# DNET_Processor.net
KiCad netlist of a schematic drawn in Altium Designer
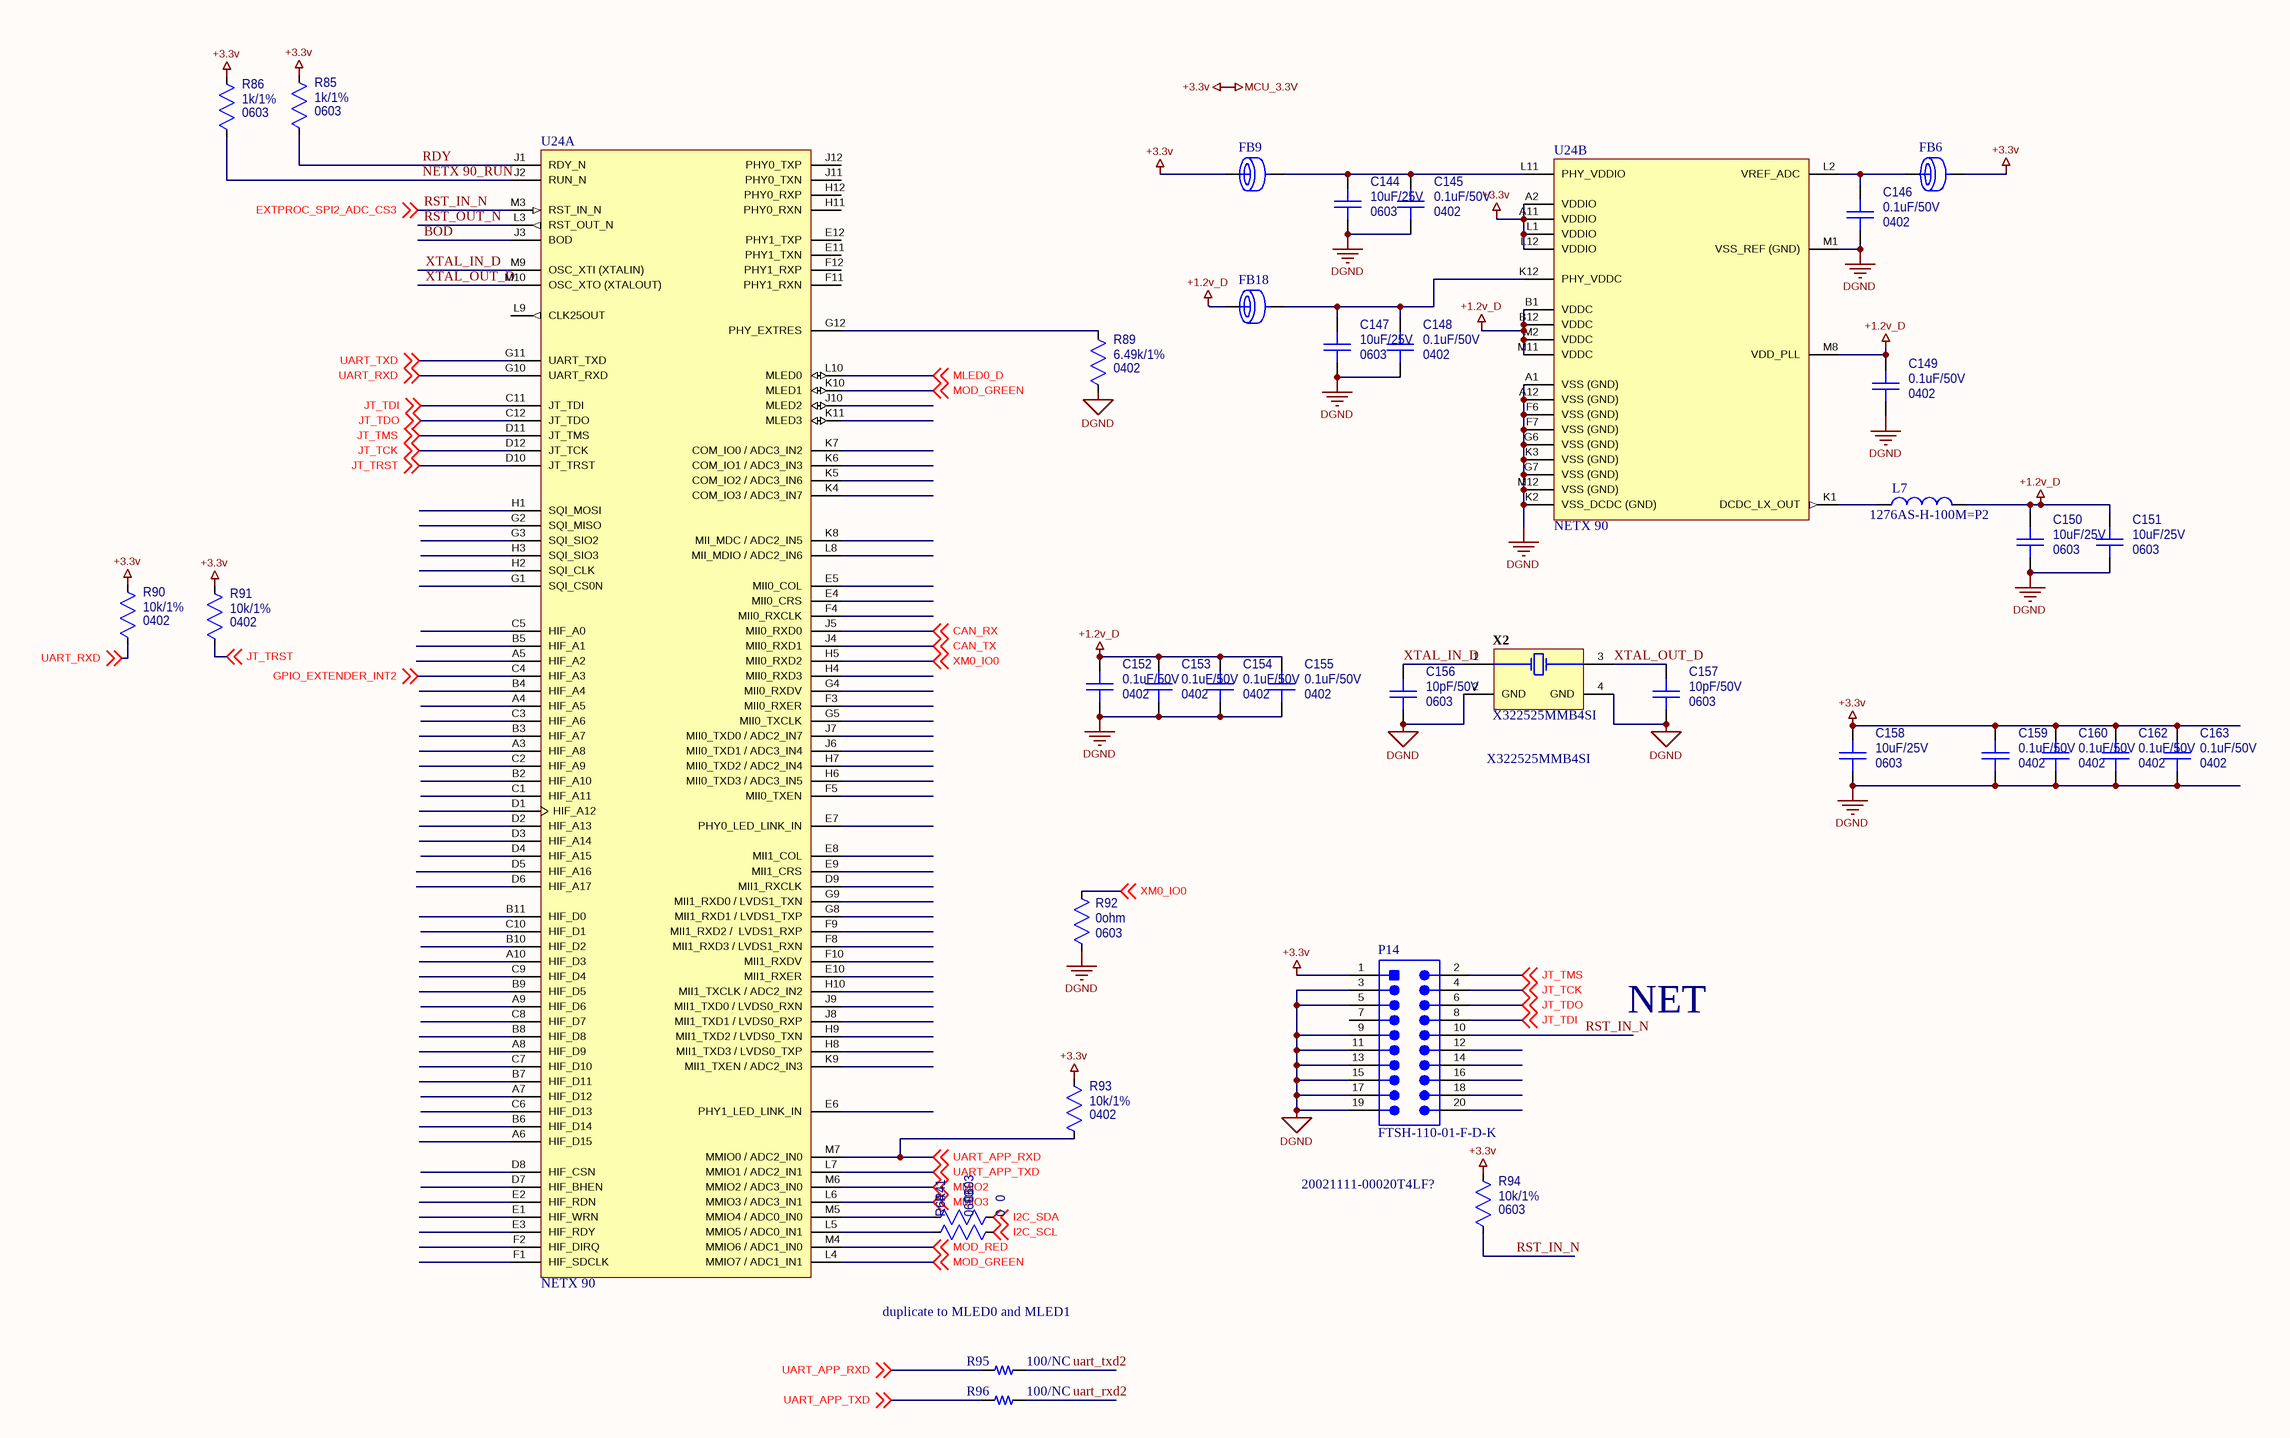
[diagram p0: DNET_Processor.SchDoc]

(export (version "E")
  (design (tool "Eeschema 10.0.6"))
  (components
    (comp (ref "C144")
      (value "10uF/25V")
      (footprint "CAPC1608X092N_0603")
      (fields
        (field (name "PARTNUMBER") "GRM188R61E106MA73D")
        (field (name "TOLERANCE") "[tol]")
        (field (name "PACKAGE") "0603")
      )
      (libsource (lib "Karl") (part "Capacitor_0603"))
    )
    (comp (ref "C145")
      (value "0.1uF/50V")
      (footprint "CAPC1005X056N_0402")
      (fields (field (name "TOLERANCE") "[tol]") (field (name "PACKAGE") "0402"))
      (libsource (lib "Karl") (part "Capacitor_0402"))
    )
    (comp (ref "C146")
      (value "0.1uF/50V")
      (footprint "CAPC1005X056N_0402")
      (fields (field (name "TOLERANCE") "[tol]") (field (name "PACKAGE") "0402"))
      (libsource (lib "Karl") (part "Capacitor_0402"))
    )
    (comp (ref "C147")
      (value "10uF/25V")
      (footprint "CAPC1608X092N_0603")
      (fields
        (field (name "PARTNUMBER") "GRM188R61E106MA73D")
        (field (name "TOLERANCE") "[tol]")
        (field (name "PACKAGE") "0603")
      )
      (libsource (lib "Karl") (part "Capacitor_0603"))
    )
    (comp (ref "C148")
      (value "0.1uF/50V")
      (footprint "CAPC1005X056N_0402")
      (fields (field (name "TOLERANCE") "[tol]") (field (name "PACKAGE") "0402"))
      (libsource (lib "Karl") (part "Capacitor_0402"))
    )
    (comp (ref "C149")
      (value "0.1uF/50V")
      (footprint "CAPC1005X056N_0402")
      (fields (field (name "TOLERANCE") "[tol]") (field (name "PACKAGE") "0402"))
      (libsource (lib "Karl") (part "Capacitor_0402"))
    )
    (comp (ref "C150")
      (value "10uF/25V")
      (footprint "CAPC1608X092N_0603")
      (fields
        (field (name "PARTNUMBER") "GRM188R61E106MA73D")
        (field (name "TOLERANCE") "[tol]")
        (field (name "PACKAGE") "0603")
      )
      (libsource (lib "Karl") (part "Capacitor_0603"))
    )
    (comp (ref "C151")
      (value "10uF/25V")
      (footprint "CAPC1608X092N_0603")
      (fields
        (field (name "PARTNUMBER") "GRM188R61E106MA73D")
        (field (name "TOLERANCE") "[tol]")
        (field (name "PACKAGE") "0603")
      )
      (libsource (lib "Karl") (part "Capacitor_0603"))
    )
    (comp (ref "C152")
      (value "0.1uF/50V")
      (footprint "CAPC1005X056N_0402")
      (fields (field (name "TOLERANCE") "[tol]") (field (name "PACKAGE") "0402"))
      (libsource (lib "Karl") (part "Capacitor_0402"))
    )
    (comp (ref "C153")
      (value "0.1uF/50V")
      (footprint "CAPC1005X056N_0402")
      (fields (field (name "TOLERANCE") "[tol]") (field (name "PACKAGE") "0402"))
      (libsource (lib "Karl") (part "Capacitor_0402"))
    )
    (comp (ref "C154")
      (value "0.1uF/50V")
      (footprint "CAPC1005X056N_0402")
      (fields (field (name "TOLERANCE") "[tol]") (field (name "PACKAGE") "0402"))
      (libsource (lib "Karl") (part "Capacitor_0402"))
    )
    (comp (ref "C155")
      (value "0.1uF/50V")
      (footprint "CAPC1005X056N_0402")
      (fields (field (name "TOLERANCE") "[tol]") (field (name "PACKAGE") "0402"))
      (libsource (lib "Karl") (part "Capacitor_0402"))
    )
    (comp (ref "C156")
      (value "10pF/50V")
      (footprint "CAPC1608X092N_0603")
      (fields (field (name "TOLERANCE") "[tol]") (field (name "PACKAGE") "0603"))
      (libsource (lib "Karl") (part "Capacitor_0603"))
    )
    (comp (ref "C157")
      (value "10pF/50V")
      (footprint "CAPC1608X092N_0603")
      (fields (field (name "TOLERANCE") "[tol]") (field (name "PACKAGE") "0603"))
      (libsource (lib "Karl") (part "Capacitor_0603"))
    )
    (comp (ref "C158")
      (value "10uF/25V")
      (footprint "CAPC1608X092N_0603")
      (fields
        (field (name "PARTNUMBER") "GRM188R61E106MA73D")
        (field (name "TOLERANCE") "[tol]")
        (field (name "PACKAGE") "0603")
      )
      (libsource (lib "Karl") (part "Capacitor_0603"))
    )
    (comp (ref "C159")
      (value "0.1uF/50V")
      (footprint "CAPC1005X056N_0402")
      (fields (field (name "TOLERANCE") "[tol]") (field (name "PACKAGE") "0402"))
      (libsource (lib "Karl") (part "Capacitor_0402"))
    )
    (comp (ref "C160")
      (value "0.1uF/50V")
      (footprint "CAPC1005X056N_0402")
      (fields (field (name "TOLERANCE") "[tol]") (field (name "PACKAGE") "0402"))
      (libsource (lib "Karl") (part "Capacitor_0402"))
    )
    (comp (ref "C162")
      (value "0.1uF/50V")
      (footprint "CAPC1005X056N_0402")
      (fields (field (name "TOLERANCE") "[tol]") (field (name "PACKAGE") "0402"))
      (libsource (lib "Karl") (part "Capacitor_0402"))
    )
    (comp (ref "C163")
      (value "0.1uF/50V")
      (footprint "CAPC1005X056N_0402")
      (fields (field (name "TOLERANCE") "[tol]") (field (name "PACKAGE") "0402"))
      (libsource (lib "Karl") (part "Capacitor_0402"))
    )
    (comp (ref "FB6")
      (value "FBC0603")
      (footprint "FBC0603")
      (fields (field (name "PARTNUMBER") "PE-0603PFB121ST"))
      (libsource (lib "Karl") (part "FBC0603"))
    )
    (comp (ref "FB9")
      (value "FBC0603")
      (footprint "FBC0603")
      (fields (field (name "PARTNUMBER") "PE-0603PFB121ST"))
      (libsource (lib "Karl") (part "FBC0603"))
    )
    (comp (ref "FB18")
      (value "FBC0603")
      (footprint "FBC0603")
      (fields (field (name "PARTNUMBER") "PE-0603PFB121ST"))
      (libsource (lib "Karl") (part "FBC0603"))
    )
    (comp (ref "L7")
      (value "1276AS-H-100M=P2")
      (footprint "MURA-IND1210_V")
      (libsource (lib "Bogen") (part "1276AS-H-100M=P2"))
    )
    (comp (ref "P14")
      (value "FTSH-110-01-F-D-K")
      (footprint "SMTC-FTSH-110-01-F-D-K_V")
      (libsource (lib "Bogen") (part "FTSH-110-01-F-D-K"))
    )
    (comp (ref "R41")
      (value "0")
      (footprint "RESC1608X055N_0603")
      (fields (field (name "TOLERANCE") "tol") (field (name "PACKAGE") "0603"))
      (libsource (lib "Karl") (part "Resistor_0603"))
    )
    (comp (ref "R64")
      (value "0")
      (footprint "RESC1608X055N_0603")
      (fields (field (name "TOLERANCE") "tol") (field (name "PACKAGE") "0603"))
      (libsource (lib "Karl") (part "Resistor_0603"))
    )
    (comp (ref "R85")
      (value "1k/1%")
      (footprint "RESC1608X055N_0603")
      (fields
        (field (name "PARTNUMBER") "RC0603FR-071KL")
        (field (name "TOLERANCE") "tol")
        (field (name "PACKAGE") "0603")
      )
      (libsource (lib "Karl") (part "Resistor_0603"))
    )
    (comp (ref "R86")
      (value "1k/1%")
      (footprint "RESC1608X055N_0603")
      (fields
        (field (name "PARTNUMBER") "RC0603FR-071KL")
        (field (name "TOLERANCE") "tol")
        (field (name "PACKAGE") "0603")
      )
      (libsource (lib "Karl") (part "Resistor_0603"))
    )
    (comp (ref "R89")
      (value "6.49k/1%")
      (footprint "RESC1005X040N_0402")
      (fields (field (name "TOLERANCE") "tol") (field (name "PACKAGE") "0402"))
      (libsource (lib "Karl") (part "Resistor_0402"))
    )
    (comp (ref "R90")
      (value "10k/1%")
      (footprint "RESC1005X040N_0402")
      (fields (field (name "TOLERANCE") "tol") (field (name "PACKAGE") "0402"))
      (libsource (lib "Karl") (part "Resistor_0402"))
    )
    (comp (ref "R91")
      (value "10k/1%")
      (footprint "RESC1005X040N_0402")
      (fields (field (name "TOLERANCE") "tol") (field (name "PACKAGE") "0402"))
      (libsource (lib "Karl") (part "Resistor_0402"))
    )
    (comp (ref "R92")
      (value "0ohm")
      (footprint "RESC1608X055N_0603")
      (fields
        (field (name "PARTNUMBER") "RC0603JR-070RL")
        (field (name "TOLERANCE") "tol")
        (field (name "PACKAGE") "0603")
      )
      (libsource (lib "Karl") (part "Resistor_0603"))
    )
    (comp (ref "R93")
      (value "10k/1%")
      (footprint "RESC1005X040N_0402")
      (fields (field (name "TOLERANCE") "tol") (field (name "PACKAGE") "0402"))
      (libsource (lib "Karl") (part "Resistor_0402"))
    )
    (comp (ref "R94")
      (value "10k/1%")
      (footprint "RESC1608X055N_0603")
      (fields (field (name "TOLERANCE") "tol") (field (name "PACKAGE") "0603"))
      (libsource (lib "Karl") (part "Resistor_0603"))
    )
    (comp (ref "R95") (value "100/NC") (footprint "RESC1608X055N_0603") (libsource (lib "JRJ_1") (part "R")))
    (comp (ref "R96") (value "100/NC") (footprint "RESC1608X055N_0603") (libsource (lib "JRJ_1") (part "R")))
    (comp (ref "U24")
      (value "NETX 90")
      (footprint "HILSCH-LFBGA144_V")
      (libsource (lib "Bogen") (part "NETX 90"))
    )
    (comp (ref "X2")
      (value "X322525MMB4SI")
      (footprint "TXC-7M-4_V")
      (libsource (lib "Bogen") (part "7M-25.000MEEQ-T"))
    )
  )
  (nets
    (net (code "1") (name "+1.2v_D") (class "Default")
      (node (ref "C149") (pin "1") (pinfunction "1_1") (pintype "passive"))
      (node (ref "C150") (pin "1") (pinfunction "1_1") (pintype "passive"))
      (node (ref "C151") (pin "1") (pinfunction "1_1") (pintype "passive"))
      (node (ref "C152") (pin "1") (pinfunction "1_1") (pintype "passive"))
      (node (ref "C153") (pin "1") (pinfunction "1_1") (pintype "passive"))
      (node (ref "C154") (pin "1") (pinfunction "1_1") (pintype "passive"))
      (node (ref "C155") (pin "1") (pinfunction "1_1") (pintype "passive"))
      (node (ref "FB18") (pin "1") (pinfunction "1_1") (pintype "passive"))
      (node (ref "L7") (pin "2") (pinfunction "2_2") (pintype "passive"))
      (node (ref "U24") (pin "B1") (pinfunction "VDDC_B1") (pintype "power_in"))
      (node (ref "U24") (pin "B12") (pinfunction "VDDC_B12") (pintype "power_in"))
      (node (ref "U24") (pin "M11") (pinfunction "VDDC_M11") (pintype "power_in"))
      (node (ref "U24") (pin "M2") (pinfunction "VDDC_M2") (pintype "power_in"))
      (node (ref "U24") (pin "M8") (pinfunction "VDD_PLL_M8") (pintype "power_in"))
    )
    (net (code "2") (name "+3.3v") (class "Default")
      (node (ref "C158") (pin "1") (pinfunction "1_1") (pintype "passive"))
      (node (ref "C159") (pin "1") (pinfunction "1_1") (pintype "passive"))
      (node (ref "C160") (pin "1") (pinfunction "1_1") (pintype "passive"))
      (node (ref "C162") (pin "1") (pinfunction "1_1") (pintype "passive"))
      (node (ref "C163") (pin "1") (pinfunction "1_1") (pintype "passive"))
      (node (ref "FB6") (pin "2") (pinfunction "2_2") (pintype "passive"))
      (node (ref "FB9") (pin "1") (pinfunction "1_1") (pintype "passive"))
      (node (ref "P14") (pin "1") (pinfunction "1_1") (pintype "passive"))
      (node (ref "R85") (pin "2") (pinfunction "2_2") (pintype "passive"))
      (node (ref "R86") (pin "2") (pinfunction "2_2") (pintype "passive"))
      (node (ref "R90") (pin "2") (pinfunction "2_2") (pintype "passive"))
      (node (ref "R91") (pin "2") (pinfunction "2_2") (pintype "passive"))
      (node (ref "R93") (pin "2") (pinfunction "2_2") (pintype "passive"))
      (node (ref "R94") (pin "2") (pinfunction "2_2") (pintype "passive"))
      (node (ref "U24") (pin "A11") (pinfunction "VDDIO_A11") (pintype "power_in"))
      (node (ref "U24") (pin "A2") (pinfunction "VDDIO_A2") (pintype "power_in"))
      (node (ref "U24") (pin "L1") (pinfunction "VDDIO_L1") (pintype "power_in"))
      (node (ref "U24") (pin "L12") (pinfunction "VDDIO_L12") (pintype "power_in"))
    )
    (net (code "3") (name "/BOD") (class "Default")
      (node (ref "U24") (pin "J3") (pinfunction "BOD_J3") (pintype "passive"))
    )
    (net (code "4") (name "/NETX 90_RUN") (class "Default")
      (node (ref "R86") (pin "1") (pinfunction "1_1") (pintype "passive"))
      (node (ref "U24") (pin "J2") (pinfunction "RUN_N_J2") (pintype "passive"))
    )
    (net (code "5") (name "/RDY") (class "Default")
      (node (ref "R85") (pin "1") (pinfunction "1_1") (pintype "passive"))
      (node (ref "U24") (pin "J1") (pinfunction "RDY_N_J1") (pintype "passive"))
    )
    (net (code "6") (name "/RST_OUT_N") (class "Default")
      (node (ref "U24") (pin "L3") (pinfunction "RST_OUT_N_L3") (pintype "output"))
    )
    (net (code "7") (name "/XTAL_IN_D") (class "Default")
      (node (ref "C156") (pin "1") (pinfunction "1_1") (pintype "passive"))
      (node (ref "U24") (pin "M9") (pinfunction "OSC_XTI_(XTALIN)_M9") (pintype "passive"))
      (node (ref "X2") (pin "1") (pinfunction "X1_1") (pintype "passive"))
    )
    (net (code "8") (name "/XTAL_OUT_D") (class "Default")
      (node (ref "C157") (pin "1") (pinfunction "1_1") (pintype "passive"))
      (node (ref "U24") (pin "M10") (pinfunction "OSC_XTO_(XTALOUT)_M10") (pintype "passive"))
      (node (ref "X2") (pin "3") (pinfunction "X2_3") (pintype "passive"))
    )
    (net (code "9") (name "/uart_rxd2") (class "Default") (node (ref "R96") (pin "2") (pintype "passive")))
    (net (code "10") (name "/uart_txd2") (class "Default") (node (ref "R95") (pin "2") (pintype "passive")))
    (net (code "11") (name "CAN_RX") (class "Default")
      (node (ref "U24") (pin "J5") (pinfunction "MII0_RXD0_J5") (pintype "passive"))
    )
    (net (code "12") (name "CAN_TX") (class "Default")
      (node (ref "U24") (pin "J4") (pinfunction "MII0_RXD1_J4") (pintype "passive"))
    )
    (net (code "13") (name "DGND") (class "Default")
      (node (ref "C144") (pin "2") (pinfunction "2_2") (pintype "passive"))
      (node (ref "C145") (pin "2") (pinfunction "2_2") (pintype "passive"))
      (node (ref "C146") (pin "2") (pinfunction "2_2") (pintype "passive"))
      (node (ref "C147") (pin "2") (pinfunction "2_2") (pintype "passive"))
      (node (ref "C148") (pin "2") (pinfunction "2_2") (pintype "passive"))
      (node (ref "C149") (pin "2") (pinfunction "2_2") (pintype "passive"))
      (node (ref "C150") (pin "2") (pinfunction "2_2") (pintype "passive"))
      (node (ref "C151") (pin "2") (pinfunction "2_2") (pintype "passive"))
      (node (ref "C152") (pin "2") (pinfunction "2_2") (pintype "passive"))
      (node (ref "C153") (pin "2") (pinfunction "2_2") (pintype "passive"))
      (node (ref "C154") (pin "2") (pinfunction "2_2") (pintype "passive"))
      (node (ref "C155") (pin "2") (pinfunction "2_2") (pintype "passive"))
      (node (ref "C156") (pin "2") (pinfunction "2_2") (pintype "passive"))
      (node (ref "C157") (pin "2") (pinfunction "2_2") (pintype "passive"))
      (node (ref "C158") (pin "2") (pinfunction "2_2") (pintype "passive"))
      (node (ref "C159") (pin "2") (pinfunction "2_2") (pintype "passive"))
      (node (ref "C160") (pin "2") (pinfunction "2_2") (pintype "passive"))
      (node (ref "C162") (pin "2") (pinfunction "2_2") (pintype "passive"))
      (node (ref "C163") (pin "2") (pinfunction "2_2") (pintype "passive"))
      (node (ref "P14") (pin "11") (pinfunction "11_11") (pintype "passive"))
      (node (ref "P14") (pin "13") (pinfunction "13_13") (pintype "passive"))
      (node (ref "P14") (pin "15") (pinfunction "15_15") (pintype "passive"))
      (node (ref "P14") (pin "17") (pinfunction "17_17") (pintype "passive"))
      (node (ref "P14") (pin "19") (pinfunction "19_19") (pintype "passive"))
      (node (ref "P14") (pin "3") (pinfunction "3_3") (pintype "passive"))
      (node (ref "P14") (pin "5") (pinfunction "5_5") (pintype "passive"))
      (node (ref "P14") (pin "9") (pinfunction "9_9") (pintype "passive"))
      (node (ref "R89") (pin "1") (pinfunction "1_1") (pintype "passive"))
      (node (ref "R92") (pin "2") (pinfunction "2_2") (pintype "passive"))
      (node (ref "U24") (pin "A1") (pinfunction "VSS_(GND)_A1") (pintype "power_in"))
      (node (ref "U24") (pin "A12") (pinfunction "VSS_(GND)_A12") (pintype "power_in"))
      (node (ref "U24") (pin "F6") (pinfunction "VSS_(GND)_F6") (pintype "power_in"))
      (node (ref "U24") (pin "F7") (pinfunction "VSS_(GND)_F7") (pintype "power_in"))
      (node (ref "U24") (pin "G6") (pinfunction "VSS_(GND)_G6") (pintype "power_in"))
      (node (ref "U24") (pin "G7") (pinfunction "VSS_(GND)_G7") (pintype "power_in"))
      (node (ref "U24") (pin "K2") (pinfunction "VSS_DCDC_(GND)_K2") (pintype "power_in"))
      (node (ref "U24") (pin "K3") (pinfunction "VSS_(GND)_K3") (pintype "power_in"))
      (node (ref "U24") (pin "M1") (pinfunction "VSS_REF_(GND)_M1") (pintype "power_in"))
      (node (ref "U24") (pin "M12") (pinfunction "VSS_(GND)_M12") (pintype "power_in"))
      (node (ref "X2") (pin "2") (pinfunction "GND_2") (pintype "power_in"))
      (node (ref "X2") (pin "4") (pinfunction "GND_4") (pintype "power_in"))
    )
    (net (code "14") (name "EXTPROC_SPI2_ADC_CS3") (class "Default")
      (node (ref "P14") (pin "10") (pinfunction "10_10") (pintype "passive"))
      (node (ref "R94") (pin "1") (pinfunction "1_1") (pintype "passive"))
      (node (ref "U24") (pin "M3") (pinfunction "RST_IN_N_M3") (pintype "input"))
    )
    (net (code "15") (name "GPIO_EXTENDER_INT2") (class "Default")
      (node (ref "U24") (pin "C4") (pinfunction "HIF_A3_C4") (pintype "passive"))
    )
    (net (code "16") (name "I2C_SCL") (class "Default")
      (node (ref "R64") (pin "1") (pinfunction "1_1") (pintype "passive"))
    )
    (net (code "17") (name "I2C_SDA") (class "Default")
      (node (ref "R41") (pin "1") (pinfunction "1_1") (pintype "passive"))
    )
    (net (code "18") (name "JT_TCK") (class "Default")
      (node (ref "P14") (pin "4") (pinfunction "4_4") (pintype "passive"))
      (node (ref "U24") (pin "D12") (pinfunction "JT_TCK_D12") (pintype "passive"))
    )
    (net (code "19") (name "JT_TDI") (class "Default")
      (node (ref "P14") (pin "8") (pinfunction "8_8") (pintype "passive"))
      (node (ref "U24") (pin "C11") (pinfunction "JT_TDI_C11") (pintype "passive"))
    )
    (net (code "20") (name "JT_TDO") (class "Default")
      (node (ref "P14") (pin "6") (pinfunction "6_6") (pintype "passive"))
      (node (ref "U24") (pin "C12") (pinfunction "JT_TDO_C12") (pintype "passive"))
    )
    (net (code "21") (name "JT_TMS") (class "Default")
      (node (ref "P14") (pin "2") (pinfunction "2_2") (pintype "passive"))
      (node (ref "U24") (pin "D11") (pinfunction "JT_TMS_D11") (pintype "passive"))
    )
    (net (code "22") (name "JT_TRST") (class "Default")
      (node (ref "R91") (pin "1") (pinfunction "1_1") (pintype "passive"))
      (node (ref "U24") (pin "D10") (pinfunction "JT_TRST_D10") (pintype "passive"))
    )
    (net (code "23") (name "MLED0_D") (class "Default")
      (node (ref "U24") (pin "L10") (pinfunction "MLED0_L10") (pintype "bidirectional"))
    )
    (net (code "24") (name "MMIO2") (class "Default")
      (node (ref "U24") (pin "M6") (pinfunction "MMIO2_/_ADC3_IN0_M6") (pintype "passive"))
    )
    (net (code "25") (name "MMIO3") (class "Default")
      (node (ref "U24") (pin "L6") (pinfunction "MMIO3_/_ADC3_IN1_L6") (pintype "passive"))
    )
    (net (code "26") (name "MOD_GREEN") (class "Default")
      (node (ref "U24") (pin "K10") (pinfunction "MLED1_K10") (pintype "bidirectional"))
      (node (ref "U24") (pin "L4") (pinfunction "MMIO7_/_ADC1_IN1_L4") (pintype "passive"))
    )
    (net (code "27") (name "MOD_RED") (class "Default")
      (node (ref "U24") (pin "M4") (pinfunction "MMIO6_/_ADC1_IN0_M4") (pintype "passive"))
    )
    (net (code "28") (name "Net-(U24A-MMIO4_{slash}_ADC0_IN0)") (class "Default")
      (node (ref "R41") (pin "2") (pinfunction "2_2") (pintype "passive"))
      (node (ref "U24") (pin "M5") (pinfunction "MMIO4_/_ADC0_IN0_M5") (pintype "passive"))
    )
    (net (code "29") (name "Net-(U24A-MMIO5_{slash}_ADC0_IN1)") (class "Default")
      (node (ref "R64") (pin "2") (pinfunction "2_2") (pintype "passive"))
      (node (ref "U24") (pin "L5") (pinfunction "MMIO5_/_ADC0_IN1_L5") (pintype "passive"))
    )
    (net (code "30") (name "Net-(U24A-PHY_EXTRES)") (class "Default")
      (node (ref "R89") (pin "2") (pinfunction "2_2") (pintype "passive"))
      (node (ref "U24") (pin "G12") (pinfunction "PHY_EXTRES_G12") (pintype "passive"))
    )
    (net (code "31") (name "Net-(U24B-DCDC_LX_OUT)") (class "Default")
      (node (ref "L7") (pin "1") (pinfunction "1_1") (pintype "passive"))
      (node (ref "U24") (pin "K1") (pinfunction "DCDC_LX_OUT_K1") (pintype "output"))
    )
    (net (code "32") (name "Net-(U24B-PHY_VDDC)") (class "Default")
      (node (ref "C147") (pin "1") (pinfunction "1_1") (pintype "passive"))
      (node (ref "C148") (pin "1") (pinfunction "1_1") (pintype "passive"))
      (node (ref "FB18") (pin "2") (pinfunction "2_2") (pintype "passive"))
      (node (ref "U24") (pin "K12") (pinfunction "PHY_VDDC_K12") (pintype "power_in"))
    )
    (net (code "33") (name "Net-(U24B-PHY_VDDIO)") (class "Default")
      (node (ref "C144") (pin "1") (pinfunction "1_1") (pintype "passive"))
      (node (ref "C145") (pin "1") (pinfunction "1_1") (pintype "passive"))
      (node (ref "FB9") (pin "2") (pinfunction "2_2") (pintype "passive"))
      (node (ref "U24") (pin "L11") (pinfunction "PHY_VDDIO_L11") (pintype "power_in"))
    )
    (net (code "34") (name "Net-(U24B-VREF_ADC)") (class "Default")
      (node (ref "C146") (pin "1") (pinfunction "1_1") (pintype "passive"))
      (node (ref "FB6") (pin "1") (pinfunction "1_1") (pintype "passive"))
      (node (ref "U24") (pin "L2") (pinfunction "VREF_ADC_L2") (pintype "power_in"))
    )
    (net (code "35") (name "UART_APP_RXD") (class "Default")
      (node (ref "R93") (pin "1") (pinfunction "1_1") (pintype "passive"))
      (node (ref "R95") (pin "1") (pintype "passive"))
      (node (ref "U24") (pin "M7") (pinfunction "MMIO0_/_ADC2_IN0_M7") (pintype "passive"))
    )
    (net (code "36") (name "UART_APP_TXD") (class "Default")
      (node (ref "R96") (pin "1") (pintype "passive"))
      (node (ref "U24") (pin "L7") (pinfunction "MMIO1_/_ADC2_IN1_L7") (pintype "passive"))
    )
    (net (code "37") (name "UART_RXD") (class "Default")
      (node (ref "R90") (pin "1") (pinfunction "1_1") (pintype "passive"))
      (node (ref "U24") (pin "G10") (pinfunction "UART_RXD_G10") (pintype "passive"))
    )
    (net (code "38") (name "UART_TXD") (class "Default")
      (node (ref "U24") (pin "G11") (pinfunction "UART_TXD_G11") (pintype "passive"))
    )
    (net (code "39") (name "XM0_IO0") (class "Default")
      (node (ref "R92") (pin "1") (pinfunction "1_1") (pintype "passive"))
      (node (ref "U24") (pin "H5") (pinfunction "MII0_RXD2_H5") (pintype "passive"))
    )
    (net (code "40") (name "unconnected-(P14-Pad7)") (class "Default")
      (node (ref "P14") (pin "7") (pinfunction "7_7") (pintype "passive"))
    )
    (net (code "41") (name "unconnected-(P14-Pad12)") (class "Default")
      (node (ref "P14") (pin "12") (pinfunction "12_12") (pintype "passive"))
    )
    (net (code "42") (name "unconnected-(P14-Pad14)") (class "Default")
      (node (ref "P14") (pin "14") (pinfunction "14_14") (pintype "passive"))
    )
    (net (code "43") (name "unconnected-(P14-Pad16)") (class "Default")
      (node (ref "P14") (pin "16") (pinfunction "16_16") (pintype "passive"))
    )
    (net (code "44") (name "unconnected-(P14-Pad18)") (class "Default")
      (node (ref "P14") (pin "18") (pinfunction "18_18") (pintype "passive"))
    )
    (net (code "45") (name "unconnected-(P14-Pad20)") (class "Default")
      (node (ref "P14") (pin "20") (pinfunction "20_20") (pintype "passive"))
    )
    (net (code "46") (name "unconnected-(U24A-CLK25OUT-PadL9)") (class "Default")
      (node (ref "U24") (pin "L9") (pinfunction "CLK25OUT_L9") (pintype "output"))
    )
    (net (code "47") (name "unconnected-(U24A-COM_IO0_{slash}_ADC3_IN2-PadK7)") (class "Default")
      (node (ref "U24") (pin "K7") (pinfunction "COM_IO0_/_ADC3_IN2_K7") (pintype "passive"))
    )
    (net (code "48") (name "unconnected-(U24A-COM_IO1_{slash}_ADC3_IN3-PadK6)") (class "Default")
      (node (ref "U24") (pin "K6") (pinfunction "COM_IO1_/_ADC3_IN3_K6") (pintype "passive"))
    )
    (net (code "49") (name "unconnected-(U24A-COM_IO2_{slash}_ADC3_IN6-PadK5)") (class "Default")
      (node (ref "U24") (pin "K5") (pinfunction "COM_IO2_/_ADC3_IN6_K5") (pintype "passive"))
    )
    (net (code "50") (name "unconnected-(U24A-COM_IO3_{slash}_ADC3_IN7-PadK4)") (class "Default")
      (node (ref "U24") (pin "K4") (pinfunction "COM_IO3_/_ADC3_IN7_K4") (pintype "passive"))
    )
    (net (code "51") (name "unconnected-(U24A-HIF_A0-PadC5)") (class "Default")
      (node (ref "U24") (pin "C5") (pinfunction "HIF_A0_C5") (pintype "passive"))
    )
    (net (code "52") (name "unconnected-(U24A-HIF_A1-PadB5)") (class "Default")
      (node (ref "U24") (pin "B5") (pinfunction "HIF_A1_B5") (pintype "passive"))
    )
    (net (code "53") (name "unconnected-(U24A-HIF_A2-PadA5)") (class "Default")
      (node (ref "U24") (pin "A5") (pinfunction "HIF_A2_A5") (pintype "passive"))
    )
    (net (code "54") (name "unconnected-(U24A-HIF_A4-PadB4)") (class "Default")
      (node (ref "U24") (pin "B4") (pinfunction "HIF_A4_B4") (pintype "passive"))
    )
    (net (code "55") (name "unconnected-(U24A-HIF_A5-PadA4)") (class "Default")
      (node (ref "U24") (pin "A4") (pinfunction "HIF_A5_A4") (pintype "passive"))
    )
    (net (code "56") (name "unconnected-(U24A-HIF_A6-PadC3)") (class "Default")
      (node (ref "U24") (pin "C3") (pinfunction "HIF_A6_C3") (pintype "passive"))
    )
    (net (code "57") (name "unconnected-(U24A-HIF_A7-PadB3)") (class "Default")
      (node (ref "U24") (pin "B3") (pinfunction "HIF_A7_B3") (pintype "passive"))
    )
    (net (code "58") (name "unconnected-(U24A-HIF_A8-PadA3)") (class "Default")
      (node (ref "U24") (pin "A3") (pinfunction "HIF_A8_A3") (pintype "passive"))
    )
    (net (code "59") (name "unconnected-(U24A-HIF_A9-PadC2)") (class "Default")
      (node (ref "U24") (pin "C2") (pinfunction "HIF_A9_C2") (pintype "passive"))
    )
    (net (code "60") (name "unconnected-(U24A-HIF_A10-PadB2)") (class "Default")
      (node (ref "U24") (pin "B2") (pinfunction "HIF_A10_B2") (pintype "passive"))
    )
    (net (code "61") (name "unconnected-(U24A-HIF_A11-PadC1)") (class "Default")
      (node (ref "U24") (pin "C1") (pinfunction "HIF_A11_C1") (pintype "passive"))
    )
    (net (code "62") (name "unconnected-(U24A-HIF_A12-PadD1)") (class "Default")
      (node (ref "U24") (pin "D1") (pinfunction "HIF_A12_D1") (pintype "passive"))
    )
    (net (code "63") (name "unconnected-(U24A-HIF_A13-PadD2)") (class "Default")
      (node (ref "U24") (pin "D2") (pinfunction "HIF_A13_D2") (pintype "passive"))
    )
    (net (code "64") (name "unconnected-(U24A-HIF_A14-PadD3)") (class "Default")
      (node (ref "U24") (pin "D3") (pinfunction "HIF_A14_D3") (pintype "passive"))
    )
    (net (code "65") (name "unconnected-(U24A-HIF_A15-PadD4)") (class "Default")
      (node (ref "U24") (pin "D4") (pinfunction "HIF_A15_D4") (pintype "passive"))
    )
    (net (code "66") (name "unconnected-(U24A-HIF_A16-PadD5)") (class "Default")
      (node (ref "U24") (pin "D5") (pinfunction "HIF_A16_D5") (pintype "passive"))
    )
    (net (code "67") (name "unconnected-(U24A-HIF_A17-PadD6)") (class "Default")
      (node (ref "U24") (pin "D6") (pinfunction "HIF_A17_D6") (pintype "passive"))
    )
    (net (code "68") (name "unconnected-(U24A-HIF_BHEN-PadD7)") (class "Default")
      (node (ref "U24") (pin "D7") (pinfunction "HIF_BHEN_D7") (pintype "passive"))
    )
    (net (code "69") (name "unconnected-(U24A-HIF_CSN-PadD8)") (class "Default")
      (node (ref "U24") (pin "D8") (pinfunction "HIF_CSN_D8") (pintype "passive"))
    )
    (net (code "70") (name "unconnected-(U24A-HIF_D0-PadB11)") (class "Default")
      (node (ref "U24") (pin "B11") (pinfunction "HIF_D0_B11") (pintype "passive"))
    )
    (net (code "71") (name "unconnected-(U24A-HIF_D1-PadC10)") (class "Default")
      (node (ref "U24") (pin "C10") (pinfunction "HIF_D1_C10") (pintype "passive"))
    )
    (net (code "72") (name "unconnected-(U24A-HIF_D2-PadB10)") (class "Default")
      (node (ref "U24") (pin "B10") (pinfunction "HIF_D2_B10") (pintype "passive"))
    )
    (net (code "73") (name "unconnected-(U24A-HIF_D3-PadA10)") (class "Default")
      (node (ref "U24") (pin "A10") (pinfunction "HIF_D3_A10") (pintype "passive"))
    )
    (net (code "74") (name "unconnected-(U24A-HIF_D4-PadC9)") (class "Default")
      (node (ref "U24") (pin "C9") (pinfunction "HIF_D4_C9") (pintype "passive"))
    )
    (net (code "75") (name "unconnected-(U24A-HIF_D5-PadB9)") (class "Default")
      (node (ref "U24") (pin "B9") (pinfunction "HIF_D5_B9") (pintype "passive"))
    )
    (net (code "76") (name "unconnected-(U24A-HIF_D6-PadA9)") (class "Default")
      (node (ref "U24") (pin "A9") (pinfunction "HIF_D6_A9") (pintype "passive"))
    )
    (net (code "77") (name "unconnected-(U24A-HIF_D7-PadC8)") (class "Default")
      (node (ref "U24") (pin "C8") (pinfunction "HIF_D7_C8") (pintype "passive"))
    )
    (net (code "78") (name "unconnected-(U24A-HIF_D8-PadB8)") (class "Default")
      (node (ref "U24") (pin "B8") (pinfunction "HIF_D8_B8") (pintype "passive"))
    )
    (net (code "79") (name "unconnected-(U24A-HIF_D9-PadA8)") (class "Default")
      (node (ref "U24") (pin "A8") (pinfunction "HIF_D9_A8") (pintype "passive"))
    )
    (net (code "80") (name "unconnected-(U24A-HIF_D10-PadC7)") (class "Default")
      (node (ref "U24") (pin "C7") (pinfunction "HIF_D10_C7") (pintype "passive"))
    )
    (net (code "81") (name "unconnected-(U24A-HIF_D11-PadB7)") (class "Default")
      (node (ref "U24") (pin "B7") (pinfunction "HIF_D11_B7") (pintype "passive"))
    )
    (net (code "82") (name "unconnected-(U24A-HIF_D12-PadA7)") (class "Default")
      (node (ref "U24") (pin "A7") (pinfunction "HIF_D12_A7") (pintype "passive"))
    )
    (net (code "83") (name "unconnected-(U24A-HIF_D13-PadC6)") (class "Default")
      (node (ref "U24") (pin "C6") (pinfunction "HIF_D13_C6") (pintype "passive"))
    )
    (net (code "84") (name "unconnected-(U24A-HIF_D14-PadB6)") (class "Default")
      (node (ref "U24") (pin "B6") (pinfunction "HIF_D14_B6") (pintype "passive"))
    )
    (net (code "85") (name "unconnected-(U24A-HIF_D15-PadA6)") (class "Default")
      (node (ref "U24") (pin "A6") (pinfunction "HIF_D15_A6") (pintype "passive"))
    )
    (net (code "86") (name "unconnected-(U24A-HIF_DIRQ-PadF2)") (class "Default")
      (node (ref "U24") (pin "F2") (pinfunction "HIF_DIRQ_F2") (pintype "passive"))
    )
    (net (code "87") (name "unconnected-(U24A-HIF_RDN-PadE2)") (class "Default")
      (node (ref "U24") (pin "E2") (pinfunction "HIF_RDN_E2") (pintype "passive"))
    )
    (net (code "88") (name "unconnected-(U24A-HIF_RDY-PadE3)") (class "Default")
      (node (ref "U24") (pin "E3") (pinfunction "HIF_RDY_E3") (pintype "passive"))
    )
    (net (code "89") (name "unconnected-(U24A-HIF_SDCLK-PadF1)") (class "Default")
      (node (ref "U24") (pin "F1") (pinfunction "HIF_SDCLK_F1") (pintype "passive"))
    )
    (net (code "90") (name "unconnected-(U24A-HIF_WRN-PadE1)") (class "Default")
      (node (ref "U24") (pin "E1") (pinfunction "HIF_WRN_E1") (pintype "passive"))
    )
    (net (code "91") (name "unconnected-(U24A-MII0_COL-PadE5)") (class "Default")
      (node (ref "U24") (pin "E5") (pinfunction "MII0_COL_E5") (pintype "passive"))
    )
    (net (code "92") (name "unconnected-(U24A-MII0_CRS-PadE4)") (class "Default")
      (node (ref "U24") (pin "E4") (pinfunction "MII0_CRS_E4") (pintype "passive"))
    )
    (net (code "93") (name "unconnected-(U24A-MII0_RXCLK-PadF4)") (class "Default")
      (node (ref "U24") (pin "F4") (pinfunction "MII0_RXCLK_F4") (pintype "passive"))
    )
    (net (code "94") (name "unconnected-(U24A-MII0_RXD3-PadH4)") (class "Default")
      (node (ref "U24") (pin "H4") (pinfunction "MII0_RXD3_H4") (pintype "passive"))
    )
    (net (code "95") (name "unconnected-(U24A-MII0_RXDV-PadG4)") (class "Default")
      (node (ref "U24") (pin "G4") (pinfunction "MII0_RXDV_G4") (pintype "passive"))
    )
    (net (code "96") (name "unconnected-(U24A-MII0_RXER-PadF3)") (class "Default")
      (node (ref "U24") (pin "F3") (pinfunction "MII0_RXER_F3") (pintype "passive"))
    )
    (net (code "97") (name "unconnected-(U24A-MII0_TXCLK-PadG5)") (class "Default")
      (node (ref "U24") (pin "G5") (pinfunction "MII0_TXCLK_G5") (pintype "passive"))
    )
    (net (code "98") (name "unconnected-(U24A-MII0_TXD0_{slash}_ADC2_IN7-PadJ7)") (class "Default")
      (node (ref "U24") (pin "J7") (pinfunction "MII0_TXD0_/_ADC2_IN7_J7") (pintype "passive"))
    )
    (net (code "99") (name "unconnected-(U24A-MII0_TXD1_{slash}_ADC3_IN4-PadJ6)") (class "Default")
      (node (ref "U24") (pin "J6") (pinfunction "MII0_TXD1_/_ADC3_IN4_J6") (pintype "passive"))
    )
    (net (code "100") (name "unconnected-(U24A-MII0_TXD2_{slash}_ADC2_IN4-PadH7)") (class "Default")
      (node (ref "U24") (pin "H7") (pinfunction "MII0_TXD2_/_ADC2_IN4_H7") (pintype "passive"))
    )
    (net (code "101") (name "unconnected-(U24A-MII0_TXD3_{slash}_ADC3_IN5-PadH6)") (class "Default")
      (node (ref "U24") (pin "H6") (pinfunction "MII0_TXD3_/_ADC3_IN5_H6") (pintype "passive"))
    )
    (net (code "102") (name "unconnected-(U24A-MII0_TXEN-PadF5)") (class "Default")
      (node (ref "U24") (pin "F5") (pinfunction "MII0_TXEN_F5") (pintype "passive"))
    )
    (net (code "103") (name "unconnected-(U24A-MII1_COL-PadE8)") (class "Default")
      (node (ref "U24") (pin "E8") (pinfunction "MII1_COL_E8") (pintype "passive"))
    )
    (net (code "104") (name "unconnected-(U24A-MII1_CRS-PadE9)") (class "Default")
      (node (ref "U24") (pin "E9") (pinfunction "MII1_CRS_E9") (pintype "passive"))
    )
    (net (code "105") (name "unconnected-(U24A-MII1_RXCLK-PadD9)") (class "Default")
      (node (ref "U24") (pin "D9") (pinfunction "MII1_RXCLK_D9") (pintype "passive"))
    )
    (net (code "106") (name "unconnected-(U24A-MII1_RXD0_{slash}_LVDS1_TXN-PadG9)") (class "Default")
      (node (ref "U24") (pin "G9") (pinfunction "MII1_RXD0_/_LVDS1_TXN_G9") (pintype "passive"))
    )
    (net (code "107") (name "unconnected-(U24A-MII1_RXD1_{slash}_LVDS1_TXP-PadG8)") (class "Default")
      (node (ref "U24") (pin "G8") (pinfunction "MII1_RXD1_/_LVDS1_TXP_G8") (pintype "passive"))
    )
    (net (code "108") (name "unconnected-(U24A-MII1_RXD2_{slash}__LVDS1_RXP-PadF9)") (class "Default")
      (node (ref "U24") (pin "F9") (pinfunction "MII1_RXD2_/__LVDS1_RXP_F9") (pintype "passive"))
    )
    (net (code "109") (name "unconnected-(U24A-MII1_RXD3_{slash}_LVDS1_RXN-PadF8)") (class "Default")
      (node (ref "U24") (pin "F8") (pinfunction "MII1_RXD3_/_LVDS1_RXN_F8") (pintype "passive"))
    )
    (net (code "110") (name "unconnected-(U24A-MII1_RXDV-PadF10)") (class "Default")
      (node (ref "U24") (pin "F10") (pinfunction "MII1_RXDV_F10") (pintype "passive"))
    )
    (net (code "111") (name "unconnected-(U24A-MII1_RXER-PadE10)") (class "Default")
      (node (ref "U24") (pin "E10") (pinfunction "MII1_RXER_E10") (pintype "passive"))
    )
    (net (code "112") (name "unconnected-(U24A-MII1_TXCLK_{slash}_ADC2_IN2-PadH10)") (class "Default")
      (node (ref "U24") (pin "H10") (pinfunction "MII1_TXCLK_/_ADC2_IN2_H10") (pintype "passive"))
    )
    (net (code "113") (name "unconnected-(U24A-MII1_TXD0_{slash}_LVDS0_RXN-PadJ9)") (class "Default")
      (node (ref "U24") (pin "J9") (pinfunction "MII1_TXD0_/_LVDS0_RXN_J9") (pintype "passive"))
    )
    (net (code "114") (name "unconnected-(U24A-MII1_TXD1_{slash}_LVDS0_RXP-PadJ8)") (class "Default")
      (node (ref "U24") (pin "J8") (pinfunction "MII1_TXD1_/_LVDS0_RXP_J8") (pintype "passive"))
    )
    (net (code "115") (name "unconnected-(U24A-MII1_TXD2_{slash}_LVDS0_TXN-PadH9)") (class "Default")
      (node (ref "U24") (pin "H9") (pinfunction "MII1_TXD2_/_LVDS0_TXN_H9") (pintype "passive"))
    )
    (net (code "116") (name "unconnected-(U24A-MII1_TXD3_{slash}_LVDS0_TXP-PadH8)") (class "Default")
      (node (ref "U24") (pin "H8") (pinfunction "MII1_TXD3_/_LVDS0_TXP_H8") (pintype "passive"))
    )
    (net (code "117") (name "unconnected-(U24A-MII1_TXEN_{slash}_ADC2_IN3-PadK9)") (class "Default")
      (node (ref "U24") (pin "K9") (pinfunction "MII1_TXEN_/_ADC2_IN3_K9") (pintype "passive"))
    )
    (net (code "118") (name "unconnected-(U24A-MII_MDC_{slash}_ADC2_IN5-PadK8)") (class "Default")
      (node (ref "U24") (pin "K8") (pinfunction "MII_MDC_/_ADC2_IN5_K8") (pintype "passive"))
    )
    (net (code "119") (name "unconnected-(U24A-MII_MDIO_{slash}_ADC2_IN6-PadL8)") (class "Default")
      (node (ref "U24") (pin "L8") (pinfunction "MII_MDIO_/_ADC2_IN6_L8") (pintype "passive"))
    )
    (net (code "120") (name "unconnected-(U24A-MLED2-PadJ10)") (class "Default")
      (node (ref "U24") (pin "J10") (pinfunction "MLED2_J10") (pintype "bidirectional"))
    )
    (net (code "121") (name "unconnected-(U24A-MLED3-PadK11)") (class "Default")
      (node (ref "U24") (pin "K11") (pinfunction "MLED3_K11") (pintype "bidirectional"))
    )
    (net (code "122") (name "unconnected-(U24A-PHY0_LED_LINK_IN-PadE7)") (class "Default")
      (node (ref "U24") (pin "E7") (pinfunction "PHY0_LED_LINK_IN_E7") (pintype "passive"))
    )
    (net (code "123") (name "unconnected-(U24A-PHY0_RXN-PadH11)") (class "Default")
      (node (ref "U24") (pin "H11") (pinfunction "PHY0_RXN_H11") (pintype "passive"))
    )
    (net (code "124") (name "unconnected-(U24A-PHY0_RXP-PadH12)") (class "Default")
      (node (ref "U24") (pin "H12") (pinfunction "PHY0_RXP_H12") (pintype "passive"))
    )
    (net (code "125") (name "unconnected-(U24A-PHY0_TXN-PadJ11)") (class "Default")
      (node (ref "U24") (pin "J11") (pinfunction "PHY0_TXN_J11") (pintype "passive"))
    )
    (net (code "126") (name "unconnected-(U24A-PHY0_TXP-PadJ12)") (class "Default")
      (node (ref "U24") (pin "J12") (pinfunction "PHY0_TXP_J12") (pintype "passive"))
    )
    (net (code "127") (name "unconnected-(U24A-PHY1_LED_LINK_IN-PadE6)") (class "Default")
      (node (ref "U24") (pin "E6") (pinfunction "PHY1_LED_LINK_IN_E6") (pintype "passive"))
    )
    (net (code "128") (name "unconnected-(U24A-PHY1_RXN-PadF11)") (class "Default")
      (node (ref "U24") (pin "F11") (pinfunction "PHY1_RXN_F11") (pintype "passive"))
    )
    (net (code "129") (name "unconnected-(U24A-PHY1_RXP-PadF12)") (class "Default")
      (node (ref "U24") (pin "F12") (pinfunction "PHY1_RXP_F12") (pintype "passive"))
    )
    (net (code "130") (name "unconnected-(U24A-PHY1_TXN-PadE11)") (class "Default")
      (node (ref "U24") (pin "E11") (pinfunction "PHY1_TXN_E11") (pintype "passive"))
    )
    (net (code "131") (name "unconnected-(U24A-PHY1_TXP-PadE12)") (class "Default")
      (node (ref "U24") (pin "E12") (pinfunction "PHY1_TXP_E12") (pintype "passive"))
    )
    (net (code "132") (name "unconnected-(U24A-SQI_CLK-PadH2)") (class "Default")
      (node (ref "U24") (pin "H2") (pinfunction "SQI_CLK_H2") (pintype "passive"))
    )
    (net (code "133") (name "unconnected-(U24A-SQI_CS0N-PadG1)") (class "Default")
      (node (ref "U24") (pin "G1") (pinfunction "SQI_CS0N_G1") (pintype "passive"))
    )
    (net (code "134") (name "unconnected-(U24A-SQI_MISO-PadG2)") (class "Default")
      (node (ref "U24") (pin "G2") (pinfunction "SQI_MISO_G2") (pintype "passive"))
    )
    (net (code "135") (name "unconnected-(U24A-SQI_MOSI-PadH1)") (class "Default")
      (node (ref "U24") (pin "H1") (pinfunction "SQI_MOSI_H1") (pintype "passive"))
    )
    (net (code "136") (name "unconnected-(U24A-SQI_SIO2-PadG3)") (class "Default")
      (node (ref "U24") (pin "G3") (pinfunction "SQI_SIO2_G3") (pintype "passive"))
    )
    (net (code "137") (name "unconnected-(U24A-SQI_SIO3-PadH3)") (class "Default")
      (node (ref "U24") (pin "H3") (pinfunction "SQI_SIO3_H3") (pintype "passive"))
    )
  )
)
